# gesamtschaltung.net
KiCad netlist of a schematic drawn in EAGLE
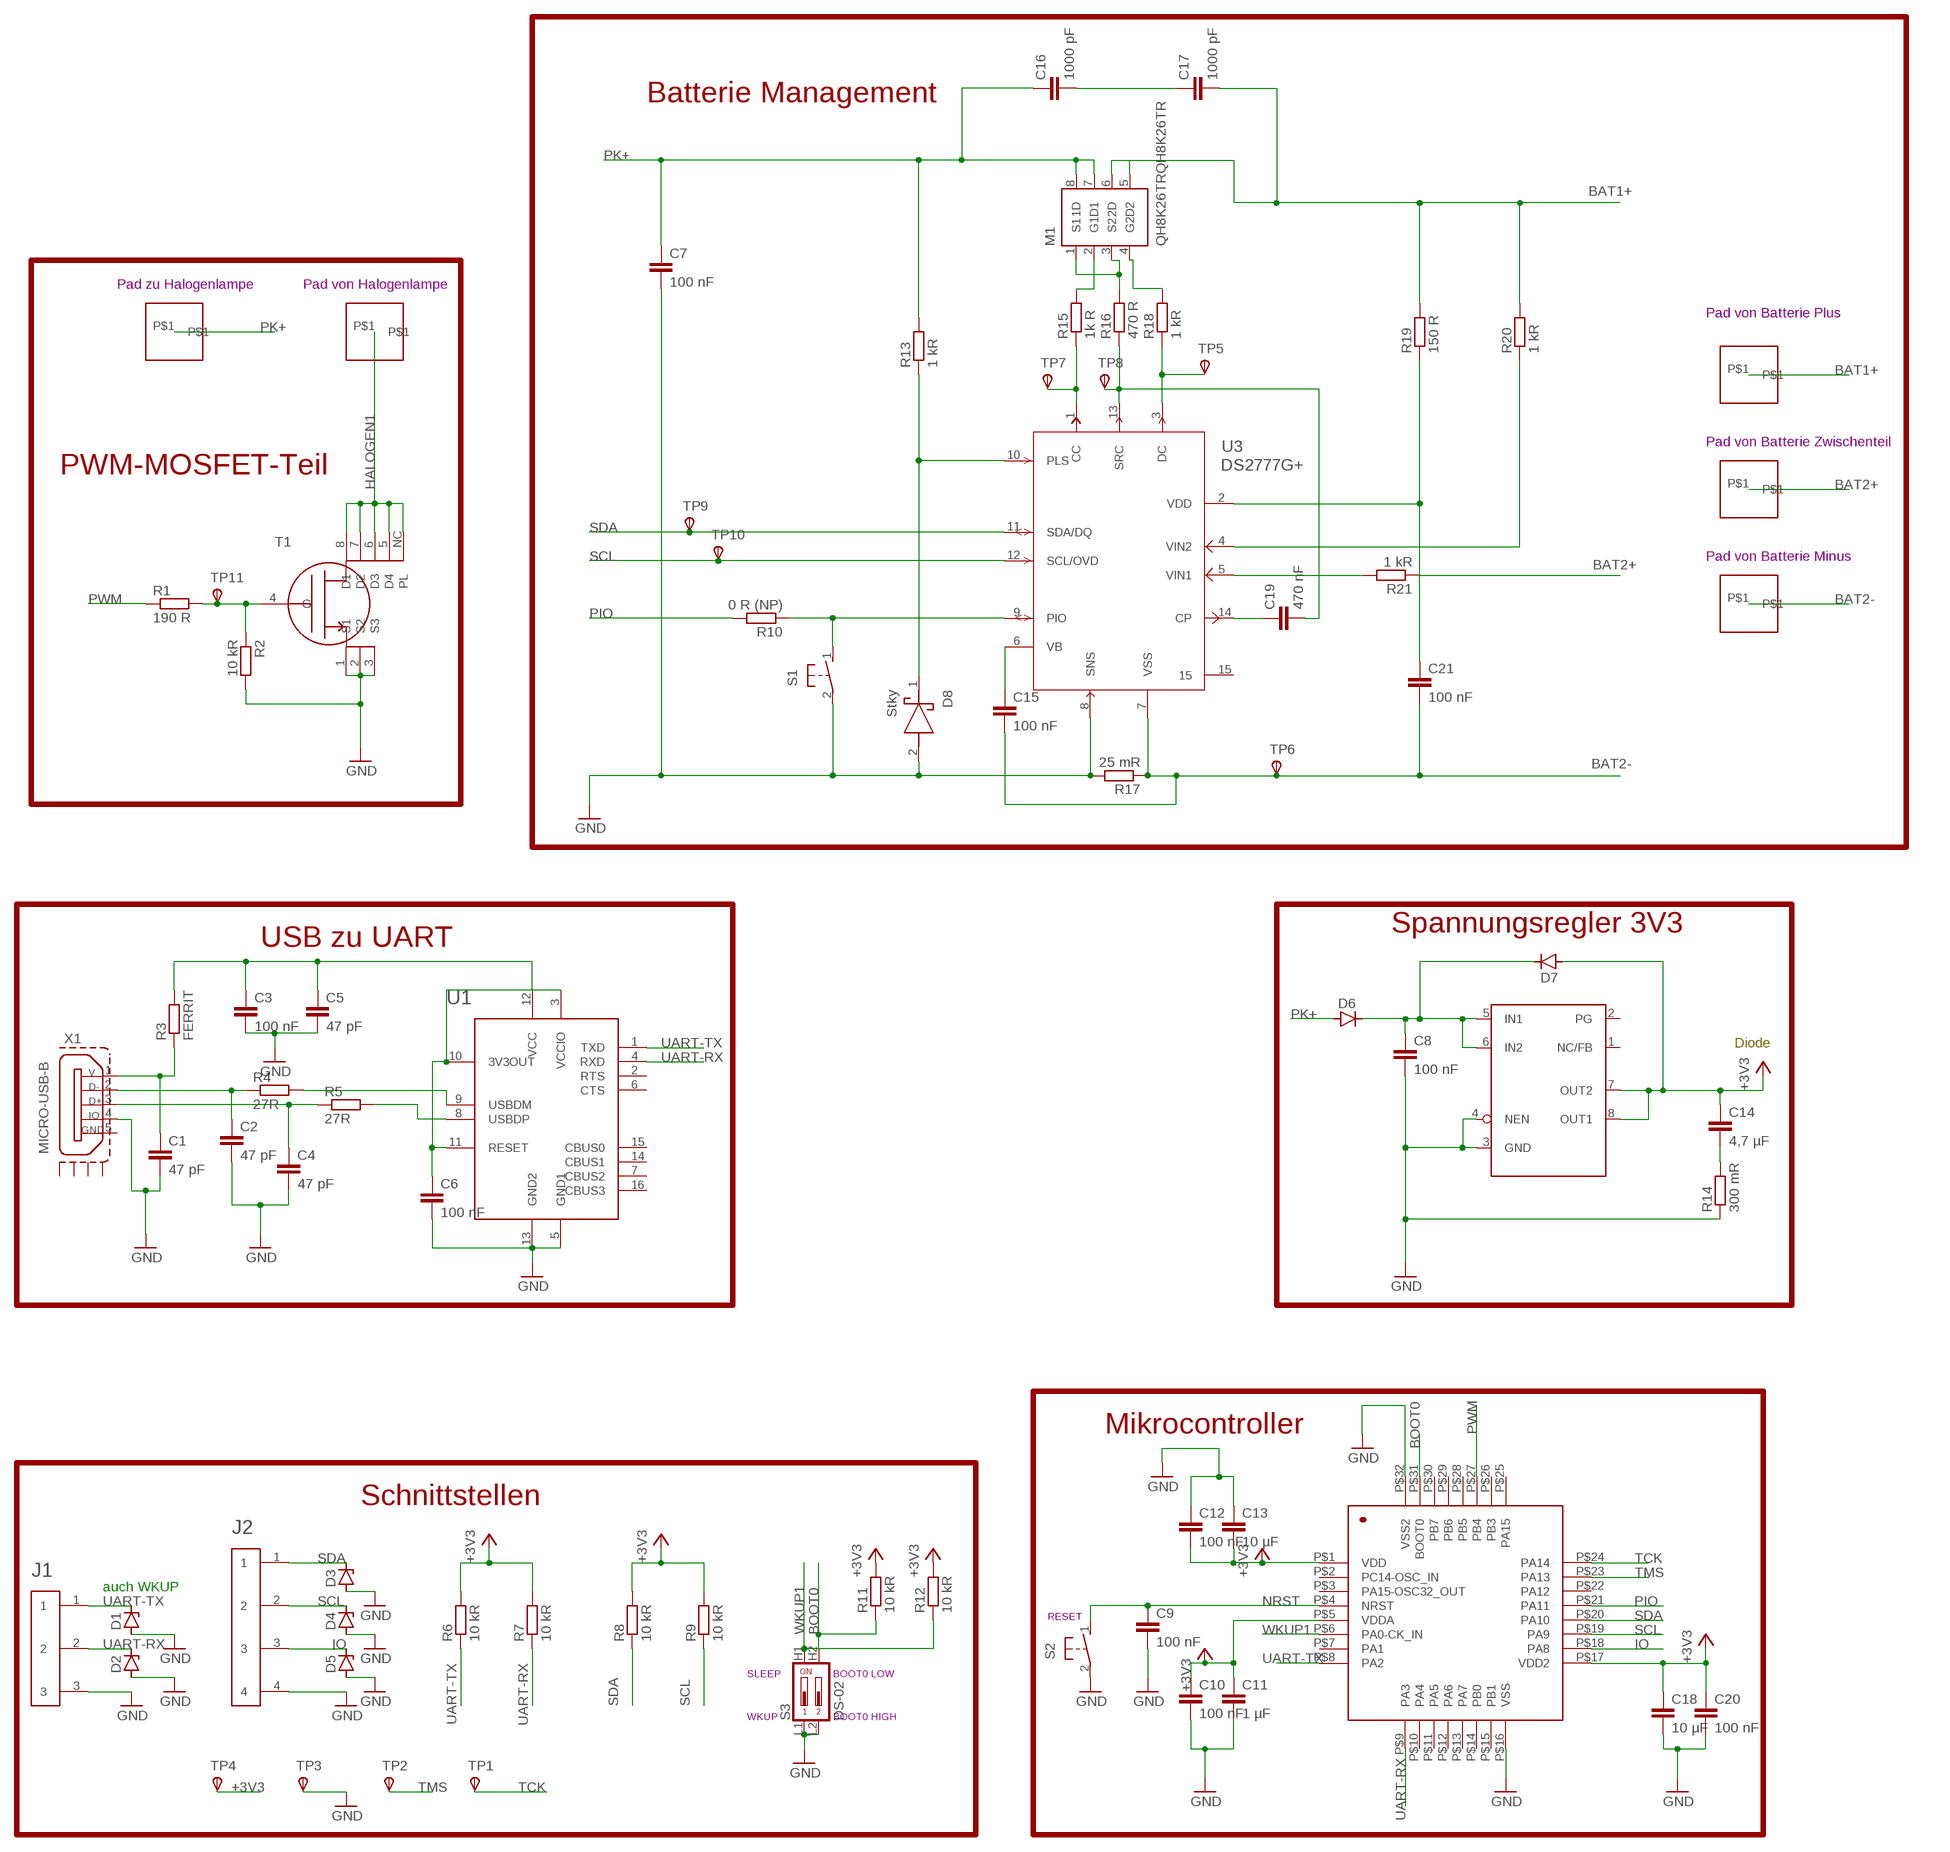
[diagram p0: schematic, sheet 1]

(export (version "E")
  (design (tool "Eeschema 10.0.6"))
  (components
    (comp (ref "C1")
      (value "47 pF")
      (footprint "eagle-import:C0603")
      (libsource (lib "eagle-import") (part "C-EUC0603"))
    )
    (comp (ref "C2")
      (value "47 pF")
      (footprint "eagle-import:C0603")
      (libsource (lib "eagle-import") (part "C-EUC0603"))
    )
    (comp (ref "C3")
      (value "100 nF")
      (footprint "eagle-import:C0603")
      (libsource (lib "eagle-import") (part "C-EUC0603"))
    )
    (comp (ref "C4")
      (value "47 pF")
      (footprint "eagle-import:C0603")
      (libsource (lib "eagle-import") (part "C-EUC0603"))
    )
    (comp (ref "C5")
      (value "47 pF")
      (footprint "eagle-import:C0603")
      (libsource (lib "eagle-import") (part "C-EUC0603"))
    )
    (comp (ref "C6")
      (value "100 nF")
      (footprint "eagle-import:C0603")
      (libsource (lib "eagle-import") (part "C-EUC0603"))
    )
    (comp (ref "C7")
      (value "100 nF")
      (footprint "eagle-import:C0603")
      (libsource (lib "eagle-import") (part "C-EUC0603"))
    )
    (comp (ref "C8")
      (value "100 nF")
      (footprint "eagle-import:C0603")
      (libsource (lib "eagle-import") (part "C-EUC0603"))
    )
    (comp (ref "C9")
      (value "100 nF")
      (footprint "eagle-import:C0603")
      (libsource (lib "eagle-import") (part "C-EUC0603"))
    )
    (comp (ref "C10")
      (value "100 nF")
      (footprint "eagle-import:C0603")
      (libsource (lib "eagle-import") (part "C-EUC0603"))
    )
    (comp (ref "C11")
      (value "1 µF")
      (footprint "eagle-import:C0603")
      (libsource (lib "eagle-import") (part "C-EUC0603"))
    )
    (comp (ref "C12")
      (value "100 nF")
      (footprint "eagle-import:C0603")
      (libsource (lib "eagle-import") (part "C-EUC0603"))
    )
    (comp (ref "C13")
      (value "10 µF")
      (footprint "eagle-import:C0603")
      (libsource (lib "eagle-import") (part "C-EUC0603"))
    )
    (comp (ref "C14")
      (value "4,7 µF")
      (footprint "eagle-import:C0603")
      (libsource (lib "eagle-import") (part "C-EUC0603"))
    )
    (comp (ref "C15")
      (value "100 nF")
      (footprint "eagle-import:C0603")
      (libsource (lib "eagle-import") (part "C-EUC0603"))
    )
    (comp (ref "C16")
      (value "1000 pF")
      (footprint "eagle-import:C0603")
      (libsource (lib "eagle-import") (part "C-EUC0603"))
    )
    (comp (ref "C17")
      (value "1000 pF")
      (footprint "eagle-import:C0603")
      (libsource (lib "eagle-import") (part "C-EUC0603"))
    )
    (comp (ref "C18")
      (value "10 µF")
      (footprint "eagle-import:C0603")
      (libsource (lib "eagle-import") (part "C-EUC0603"))
    )
    (comp (ref "C19")
      (value "470 nF")
      (footprint "eagle-import:C0603")
      (libsource (lib "eagle-import") (part "C-EUC0603"))
    )
    (comp (ref "C20")
      (value "100 nF")
      (footprint "eagle-import:C0603")
      (libsource (lib "eagle-import") (part "C-EUC0603"))
    )
    (comp (ref "C21")
      (value "100 nF")
      (footprint "eagle-import:C0603")
      (libsource (lib "eagle-import") (part "C-EUC0603"))
    )
    (comp (ref "D1")
      (value "TVS-3V5")
      (footprint "eagle-import:TVS-FOOT")
      (libsource (lib "eagle-import") (part "TVS-3V5"))
    )
    (comp (ref "D2")
      (value "TVS-3V5")
      (footprint "eagle-import:TVS-FOOT")
      (libsource (lib "eagle-import") (part "TVS-3V5"))
    )
    (comp (ref "D3")
      (value "TVS-3V5")
      (footprint "eagle-import:TVS-FOOT")
      (libsource (lib "eagle-import") (part "TVS-3V5"))
    )
    (comp (ref "D4")
      (value "TVS-3V5")
      (footprint "eagle-import:TVS-FOOT")
      (libsource (lib "eagle-import") (part "TVS-3V5"))
    )
    (comp (ref "D5")
      (value "TVS-3V5")
      (footprint "eagle-import:TVS-FOOT")
      (libsource (lib "eagle-import") (part "TVS-3V5"))
    )
    (comp (ref "D6")
      (value "DIODE-SILIZIUM")
      (footprint "eagle-import:TVS-FOOT")
      (libsource (lib "eagle-import") (part "DIODE-SILIZIUM"))
    )
    (comp (ref "D7")
      (value "DIODE-SILIZIUM")
      (footprint "eagle-import:TVS-FOOT")
      (libsource (lib "eagle-import") (part "DIODE-SILIZIUM"))
    )
    (comp (ref "D8")
      (value "Stky")
      (footprint "eagle-import:SOD3715X135N")
      (libsource (lib "eagle-import") (part "BAT54W-HG3-18SCHOTTKY"))
    )
    (comp (ref "J1")
      (value "3PIN")
      (footprint "eagle-import:HDRV3W64P254_1X3_762X254X854B")
      (libsource (lib "eagle-import") (part "3PIN"))
    )
    (comp (ref "J2")
      (value "4PIN-MALE")
      (footprint "eagle-import:4P-MALE-FOOT")
      (libsource (lib "eagle-import") (part "4PIN-MALE"))
    )
    (comp (ref "M1")
      (value "QH8K26TRQH8K26TR")
      (footprint "eagle-import:SOTFL65P280X85-8N")
      (libsource (lib "eagle-import") (part "QH8K26TRQH8K26TR"))
    )
    (comp (ref "MC1")
      (value "STM32L031K6T6")
      (footprint "eagle-import:LQFP32")
      (libsource (lib "eagle-import") (part "STM32L031K6T6"))
    )
    (comp (ref "P1")
      (value "PAD-3MM")
      (footprint "eagle-import:PAD-3MM")
      (libsource (lib "eagle-import") (part "PAD-3MM"))
    )
    (comp (ref "P2")
      (value "PAD-3MM")
      (footprint "eagle-import:PAD-3MM")
      (libsource (lib "eagle-import") (part "PAD-3MM"))
    )
    (comp (ref "P3")
      (value "PAD-3MM")
      (footprint "eagle-import:PAD-3MM")
      (libsource (lib "eagle-import") (part "PAD-3MM"))
    )
    (comp (ref "P4")
      (value "PAD-3MM")
      (footprint "eagle-import:PAD-3MM")
      (libsource (lib "eagle-import") (part "PAD-3MM"))
    )
    (comp (ref "P5")
      (value "PAD-3MM")
      (footprint "eagle-import:PAD-3MM")
      (libsource (lib "eagle-import") (part "PAD-3MM"))
    )
    (comp (ref "R1")
      (value "190 R")
      (footprint "eagle-import:R0603")
      (libsource (lib "eagle-import") (part "R-EU_R0603"))
    )
    (comp (ref "R2")
      (value "10 kR")
      (footprint "eagle-import:R0603")
      (libsource (lib "eagle-import") (part "R-EU_R0603"))
    )
    (comp (ref "R3")
      (value "FERRIT")
      (footprint "eagle-import:R0603")
      (libsource (lib "eagle-import") (part "R-EU_R0603"))
    )
    (comp (ref "R4")
      (value "27R")
      (footprint "eagle-import:R0603")
      (libsource (lib "eagle-import") (part "R-EU_R0603"))
    )
    (comp (ref "R5")
      (value "27R")
      (footprint "eagle-import:R0603")
      (libsource (lib "eagle-import") (part "R-EU_R0603"))
    )
    (comp (ref "R6")
      (value "10 kR")
      (footprint "eagle-import:R0603")
      (libsource (lib "eagle-import") (part "R-EU_R0603"))
    )
    (comp (ref "R7")
      (value "10 kR")
      (footprint "eagle-import:R0603")
      (libsource (lib "eagle-import") (part "R-EU_R0603"))
    )
    (comp (ref "R8")
      (value "10 kR")
      (footprint "eagle-import:R0603")
      (libsource (lib "eagle-import") (part "R-EU_R0603"))
    )
    (comp (ref "R9")
      (value "10 kR")
      (footprint "eagle-import:R0603")
      (libsource (lib "eagle-import") (part "R-EU_R0603"))
    )
    (comp (ref "R10")
      (value "0 R (NP)")
      (footprint "eagle-import:R0603")
      (libsource (lib "eagle-import") (part "R-EU_R0603"))
    )
    (comp (ref "R11")
      (value "10 kR")
      (footprint "eagle-import:R0603")
      (libsource (lib "eagle-import") (part "R-EU_R0603"))
    )
    (comp (ref "R12")
      (value "10 kR")
      (footprint "eagle-import:R0603")
      (libsource (lib "eagle-import") (part "R-EU_R0603"))
    )
    (comp (ref "R13")
      (value "1 kR")
      (footprint "eagle-import:R0603")
      (libsource (lib "eagle-import") (part "R-EU_R0603"))
    )
    (comp (ref "R14")
      (value "300 mR")
      (footprint "eagle-import:R0603")
      (libsource (lib "eagle-import") (part "R-EU_R0603"))
    )
    (comp (ref "R15")
      (value "1k R")
      (footprint "eagle-import:R0603")
      (libsource (lib "eagle-import") (part "R-EU_R0603"))
    )
    (comp (ref "R16")
      (value "470 R")
      (footprint "eagle-import:R0603")
      (libsource (lib "eagle-import") (part "R-EU_R0603"))
    )
    (comp (ref "R17")
      (value "25 mR")
      (footprint "eagle-import:R0603")
      (libsource (lib "eagle-import") (part "R-EU_R0603"))
    )
    (comp (ref "R18")
      (value "1 kR")
      (footprint "eagle-import:R0603")
      (libsource (lib "eagle-import") (part "R-EU_R0603"))
    )
    (comp (ref "R19")
      (value "150 R")
      (footprint "eagle-import:R0603")
      (libsource (lib "eagle-import") (part "R-EU_R0603"))
    )
    (comp (ref "R20")
      (value "1 kR")
      (footprint "eagle-import:R0603")
      (libsource (lib "eagle-import") (part "R-EU_R0603"))
    )
    (comp (ref "R21")
      (value "1 kR")
      (footprint "eagle-import:R0603")
      (libsource (lib "eagle-import") (part "R-EU_R0603"))
    )
    (comp (ref "S1")
      (value "BUTTON")
      (footprint "eagle-import:BUTTON")
      (libsource (lib "eagle-import") (part "BUTTON"))
    )
    (comp (ref "S2")
      (value "BUTTON")
      (footprint "eagle-import:BUTTON")
      (libsource (lib "eagle-import") (part "BUTTON"))
    )
    (comp (ref "S3")
      (value "DS-02")
      (footprint "eagle-import:DS-02")
      (libsource (lib "eagle-import") (part "DS-02"))
    )
    (comp (ref "T1")
      (value "POWER-MOS")
      (footprint "eagle-import:SO-8")
      (libsource (lib "eagle-import") (part "POWER-MOS"))
    )
    (comp (ref "TP1")
      (value "TPSTP20R")
      (footprint "eagle-import:TP20R")
      (libsource (lib "eagle-import") (part "TPSTP20R"))
    )
    (comp (ref "TP2")
      (value "TPSTP20R")
      (footprint "eagle-import:TP20R")
      (libsource (lib "eagle-import") (part "TPSTP20R"))
    )
    (comp (ref "TP3")
      (value "TPSTP20R")
      (footprint "eagle-import:TP20R")
      (libsource (lib "eagle-import") (part "TPSTP20R"))
    )
    (comp (ref "TP4")
      (value "TPSTP20R")
      (footprint "eagle-import:TP20R")
      (libsource (lib "eagle-import") (part "TPSTP20R"))
    )
    (comp (ref "TP5")
      (value "TPSTP10R")
      (footprint "eagle-import:TP10R")
      (libsource (lib "eagle-import") (part "TPSTP10R"))
    )
    (comp (ref "TP6")
      (value "TPSTP10R")
      (footprint "eagle-import:TP10R")
      (libsource (lib "eagle-import") (part "TPSTP10R"))
    )
    (comp (ref "TP7")
      (value "TPSTP10R")
      (footprint "eagle-import:TP10R")
      (libsource (lib "eagle-import") (part "TPSTP10R"))
    )
    (comp (ref "TP8")
      (value "TPSTP10R")
      (footprint "eagle-import:TP10R")
      (libsource (lib "eagle-import") (part "TPSTP10R"))
    )
    (comp (ref "TP9")
      (value "TPSTP10R")
      (footprint "eagle-import:TP10R")
      (libsource (lib "eagle-import") (part "TPSTP10R"))
    )
    (comp (ref "TP10")
      (value "TPSTP10R")
      (footprint "eagle-import:TP10R")
      (libsource (lib "eagle-import") (part "TPSTP10R"))
    )
    (comp (ref "TP11")
      (value "TPSTP10R")
      (footprint "eagle-import:TP10R")
      (libsource (lib "eagle-import") (part "TPSTP10R"))
    )
    (comp (ref "U1")
      (value "FT230X")
      (footprint "eagle-import:SSOP16")
      (libsource (lib "eagle-import") (part "FT230X"))
    )
    (comp (ref "U2")
      (value "TPS76633DR")
      (footprint "eagle-import:TPS766FOOTPRINT")
      (libsource (lib "eagle-import") (part "TPS76633DR"))
    )
    (comp (ref "U3")
      (value "DS2777G+")
      (footprint "eagle-import:DS2777_TDFN-15-OWN")
      (libsource (lib "eagle-import") (part "DS2777G+"))
    )
    (comp (ref "X1")
      (value "MICRO-USB-B")
      (footprint "eagle-import:MICROUSBFOOT")
      (libsource (lib "eagle-import") (part "MICRO-USB-B"))
    )
  )
  (nets
    (net (code "1") (name "+3V3") (class "Default")
      (node (ref "C10") (pin "1") (pinfunction "1_1") (pintype "passive"))
      (node (ref "C11") (pin "1") (pinfunction "1_1") (pintype "passive"))
      (node (ref "C12") (pin "2") (pinfunction "2_2") (pintype "passive"))
      (node (ref "C13") (pin "2") (pinfunction "2_2") (pintype "passive"))
      (node (ref "C14") (pin "1") (pinfunction "1_1") (pintype "passive"))
      (node (ref "C18") (pin "1") (pinfunction "1_1") (pintype "passive"))
      (node (ref "C20") (pin "1") (pinfunction "1_1") (pintype "passive"))
      (node (ref "D7") (pin "A") (pinfunction "A_A") (pintype "passive"))
      (node (ref "MC1") (pin "P$1") (pinfunction "VDD_P$1") (pintype "bidirectional"))
      (node (ref "MC1") (pin "P$17") (pinfunction "VDD2_P$17") (pintype "bidirectional"))
      (node (ref "MC1") (pin "P$5") (pinfunction "VDDA_P$5") (pintype "bidirectional"))
      (node (ref "R11") (pin "2") (pinfunction "2_2") (pintype "passive"))
      (node (ref "R12") (pin "2") (pinfunction "2_2") (pintype "passive"))
      (node (ref "R6") (pin "2") (pinfunction "2_2") (pintype "passive"))
      (node (ref "R7") (pin "2") (pinfunction "2_2") (pintype "passive"))
      (node (ref "R8") (pin "2") (pinfunction "2_2") (pintype "passive"))
      (node (ref "R9") (pin "2") (pinfunction "2_2") (pintype "passive"))
      (node (ref "TP4") (pin "TP") (pinfunction "PP_TP") (pintype "input"))
      (node (ref "U2") (pin "7") (pinfunction "OUT2_7") (pintype "bidirectional"))
      (node (ref "U2") (pin "8") (pinfunction "OUT1_8") (pintype "bidirectional"))
    )
    (net (code "2") (name "/BAT1+") (class "Default")
      (node (ref "C17") (pin "2") (pinfunction "2_2") (pintype "passive"))
      (node (ref "M1") (pin "5") (pinfunction "D2_5") (pintype "passive"))
      (node (ref "M1") (pin "6") (pinfunction "2D_6") (pintype "passive"))
      (node (ref "P3") (pin "P$1") (pinfunction "P$1_P$1") (pintype "bidirectional"))
      (node (ref "R19") (pin "2") (pinfunction "2_2") (pintype "passive"))
      (node (ref "R20") (pin "2") (pinfunction "2_2") (pintype "passive"))
    )
    (net (code "3") (name "/BAT2+") (class "Default")
      (node (ref "P4") (pin "P$1") (pinfunction "P$1_P$1") (pintype "bidirectional"))
      (node (ref "R21") (pin "1") (pinfunction "1_1") (pintype "passive"))
    )
    (net (code "4") (name "/BAT2-") (class "Default")
      (node (ref "C15") (pin "2") (pinfunction "2_2") (pintype "passive"))
      (node (ref "C21") (pin "2") (pinfunction "2_2") (pintype "passive"))
      (node (ref "P5") (pin "P$1") (pinfunction "P$1_P$1") (pintype "bidirectional"))
      (node (ref "R17") (pin "1") (pinfunction "1_1") (pintype "passive"))
      (node (ref "TP6") (pin "TP") (pinfunction "PP_TP") (pintype "input"))
      (node (ref "U3") (pin "7") (pinfunction "VSS_7") (pintype "power_in"))
    )
    (net (code "5") (name "/BOOT0") (class "Default")
      (node (ref "MC1") (pin "P$31") (pinfunction "BOOT0_P$31") (pintype "bidirectional"))
      (node (ref "R11") (pin "1") (pinfunction "1_1") (pintype "passive"))
      (node (ref "S3") (pin "H2") (pinfunction "H2_H2") (pintype "passive"))
    )
    (net (code "6") (name "/HALOGEN1") (class "Default")
      (node (ref "P2") (pin "P$1") (pinfunction "P$1_P$1") (pintype "bidirectional"))
      (node (ref "T1") (pin "5") (pinfunction "D4_5") (pintype "bidirectional"))
      (node (ref "T1") (pin "6") (pinfunction "D3_6") (pintype "bidirectional"))
      (node (ref "T1") (pin "7") (pinfunction "D2_7") (pintype "bidirectional"))
      (node (ref "T1") (pin "8") (pinfunction "D1_8") (pintype "bidirectional"))
      (node (ref "T1") (pin "NC") (pinfunction "PL_NC") (pintype "bidirectional"))
    )
    (net (code "7") (name "/IO") (class "Default")
      (node (ref "D5") (pin "K") (pinfunction "K_K") (pintype "passive"))
      (node (ref "J2") (pin "3") (pinfunction "3_3") (pintype "bidirectional"))
      (node (ref "MC1") (pin "P$18") (pinfunction "PA8_P$18") (pintype "bidirectional"))
    )
    (net (code "8") (name "/NRST") (class "Default")
      (node (ref "C9") (pin "1") (pinfunction "1_1") (pintype "passive"))
      (node (ref "MC1") (pin "P$4") (pinfunction "NRST_P$4") (pintype "bidirectional"))
      (node (ref "S2") (pin "1") (pinfunction "H_1") (pintype "passive"))
    )
    (net (code "9") (name "/PIO") (class "Default")
      (node (ref "MC1") (pin "P$21") (pinfunction "PA11_P$21") (pintype "bidirectional"))
      (node (ref "R10") (pin "2") (pinfunction "2_2") (pintype "passive"))
    )
    (net (code "10") (name "/PK+") (class "Default")
      (node (ref "C16") (pin "1") (pinfunction "1_1") (pintype "passive"))
      (node (ref "C7") (pin "1") (pinfunction "1_1") (pintype "passive"))
      (node (ref "D6") (pin "A") (pinfunction "A_A") (pintype "passive"))
      (node (ref "M1") (pin "7") (pinfunction "D1_7") (pintype "passive"))
      (node (ref "M1") (pin "8") (pinfunction "1D_8") (pintype "passive"))
      (node (ref "P1") (pin "P$1") (pinfunction "P$1_P$1") (pintype "bidirectional"))
      (node (ref "R13") (pin "2") (pinfunction "2_2") (pintype "passive"))
    )
    (net (code "11") (name "/PWM") (class "Default")
      (node (ref "MC1") (pin "P$27") (pinfunction "PB4_P$27") (pintype "bidirectional"))
      (node (ref "R1") (pin "1") (pinfunction "1_1") (pintype "passive"))
    )
    (net (code "12") (name "/SCL") (class "Default")
      (node (ref "D4") (pin "K") (pinfunction "K_K") (pintype "passive"))
      (node (ref "J2") (pin "2") (pinfunction "2_2") (pintype "bidirectional"))
      (node (ref "MC1") (pin "P$19") (pinfunction "PA9_P$19") (pintype "bidirectional"))
      (node (ref "R9") (pin "1") (pinfunction "1_1") (pintype "passive"))
      (node (ref "TP10") (pin "TP") (pinfunction "PP_TP") (pintype "input"))
      (node (ref "U3") (pin "12") (pinfunction "SCL/OVD_12") (pintype "input"))
    )
    (net (code "13") (name "/SDA") (class "Default")
      (node (ref "D3") (pin "K") (pinfunction "K_K") (pintype "passive"))
      (node (ref "J2") (pin "1") (pinfunction "1_1") (pintype "bidirectional"))
      (node (ref "MC1") (pin "P$20") (pinfunction "PA10_P$20") (pintype "bidirectional"))
      (node (ref "R8") (pin "1") (pinfunction "1_1") (pintype "passive"))
      (node (ref "TP9") (pin "TP") (pinfunction "PP_TP") (pintype "input"))
      (node (ref "U3") (pin "11") (pinfunction "SDA/DQ_11") (pintype "bidirectional"))
    )
    (net (code "14") (name "/TCK") (class "Default")
      (node (ref "MC1") (pin "P$24") (pinfunction "PA14_P$24") (pintype "bidirectional"))
      (node (ref "TP1") (pin "TP") (pinfunction "PP_TP") (pintype "input"))
    )
    (net (code "15") (name "/TMS") (class "Default")
      (node (ref "MC1") (pin "P$23") (pinfunction "PA13_P$23") (pintype "bidirectional"))
      (node (ref "TP2") (pin "TP") (pinfunction "PP_TP") (pintype "input"))
    )
    (net (code "16") (name "/UART-RX") (class "Default")
      (node (ref "D2") (pin "K") (pinfunction "K_K") (pintype "passive"))
      (node (ref "J1") (pin "2") (pinfunction "2_2") (pintype "bidirectional"))
      (node (ref "MC1") (pin "P$9") (pinfunction "PA3_P$9") (pintype "bidirectional"))
      (node (ref "R7") (pin "1") (pinfunction "1_1") (pintype "passive"))
      (node (ref "U1") (pin "4") (pinfunction "RXD_4") (pintype "bidirectional"))
    )
    (net (code "17") (name "/UART-TX") (class "Default")
      (node (ref "D1") (pin "K") (pinfunction "K_K") (pintype "passive"))
      (node (ref "J1") (pin "1") (pinfunction "1_1") (pintype "bidirectional"))
      (node (ref "MC1") (pin "P$8") (pinfunction "PA2_P$8") (pintype "bidirectional"))
      (node (ref "R6") (pin "1") (pinfunction "1_1") (pintype "passive"))
      (node (ref "U1") (pin "1") (pinfunction "TXD_1") (pintype "bidirectional"))
    )
    (net (code "18") (name "/WKUP1") (class "Default")
      (node (ref "MC1") (pin "P$6") (pinfunction "PA0-CK_IN_P$6") (pintype "bidirectional"))
      (node (ref "R12") (pin "1") (pinfunction "1_1") (pintype "passive"))
      (node (ref "S3") (pin "H1") (pinfunction "H1_H1") (pintype "passive"))
    )
    (net (code "19") (name "GND") (class "Default")
      (node (ref "C1") (pin "2") (pinfunction "2_2") (pintype "passive"))
      (node (ref "C10") (pin "2") (pinfunction "2_2") (pintype "passive"))
      (node (ref "C11") (pin "2") (pinfunction "2_2") (pintype "passive"))
      (node (ref "C12") (pin "1") (pinfunction "1_1") (pintype "passive"))
      (node (ref "C13") (pin "1") (pinfunction "1_1") (pintype "passive"))
      (node (ref "C18") (pin "2") (pinfunction "2_2") (pintype "passive"))
      (node (ref "C2") (pin "2") (pinfunction "2_2") (pintype "passive"))
      (node (ref "C20") (pin "2") (pinfunction "2_2") (pintype "passive"))
      (node (ref "C3") (pin "2") (pinfunction "2_2") (pintype "passive"))
      (node (ref "C4") (pin "2") (pinfunction "2_2") (pintype "passive"))
      (node (ref "C5") (pin "2") (pinfunction "2_2") (pintype "passive"))
      (node (ref "C6") (pin "2") (pinfunction "2_2") (pintype "passive"))
      (node (ref "C7") (pin "2") (pinfunction "2_2") (pintype "passive"))
      (node (ref "C8") (pin "2") (pinfunction "2_2") (pintype "passive"))
      (node (ref "C9") (pin "2") (pinfunction "2_2") (pintype "passive"))
      (node (ref "D1") (pin "A") (pinfunction "A_A") (pintype "passive"))
      (node (ref "D2") (pin "A") (pinfunction "A_A") (pintype "passive"))
      (node (ref "D3") (pin "A") (pinfunction "A_A") (pintype "passive"))
      (node (ref "D4") (pin "A") (pinfunction "A_A") (pintype "passive"))
      (node (ref "D5") (pin "A") (pinfunction "A_A") (pintype "passive"))
      (node (ref "D8") (pin "2") (pinfunction "A_2") (pintype "bidirectional"))
      (node (ref "J1") (pin "3") (pinfunction "3_3") (pintype "bidirectional"))
      (node (ref "J2") (pin "4") (pinfunction "4_4") (pintype "bidirectional"))
      (node (ref "MC1") (pin "P$16") (pinfunction "VSS_P$16") (pintype "bidirectional"))
      (node (ref "MC1") (pin "P$32") (pinfunction "VSS2_P$32") (pintype "bidirectional"))
      (node (ref "R14") (pin "1") (pinfunction "1_1") (pintype "passive"))
      (node (ref "R17") (pin "2") (pinfunction "2_2") (pintype "passive"))
      (node (ref "R2") (pin "2") (pinfunction "2_2") (pintype "passive"))
      (node (ref "S1") (pin "2") (pinfunction "L_2") (pintype "passive"))
      (node (ref "S2") (pin "2") (pinfunction "L_2") (pintype "passive"))
      (node (ref "S3") (pin "L1") (pinfunction "L1_L1") (pintype "passive"))
      (node (ref "S3") (pin "L2") (pinfunction "L2_L2") (pintype "passive"))
      (node (ref "T1") (pin "1") (pinfunction "S1_1") (pintype "bidirectional"))
      (node (ref "T1") (pin "2") (pinfunction "S2_2") (pintype "bidirectional"))
      (node (ref "T1") (pin "3") (pinfunction "S3_3") (pintype "bidirectional"))
      (node (ref "TP3") (pin "TP") (pinfunction "PP_TP") (pintype "input"))
      (node (ref "U1") (pin "13") (pinfunction "GND2_13") (pintype "bidirectional"))
      (node (ref "U1") (pin "5") (pinfunction "GND1_5") (pintype "bidirectional"))
      (node (ref "U2") (pin "3") (pinfunction "GND_3") (pintype "bidirectional"))
      (node (ref "U2") (pin "4") (pinfunction "NEN_4") (pintype "bidirectional"))
      (node (ref "U3") (pin "8") (pinfunction "SNS_8") (pintype "input"))
      (node (ref "X1") (pin "4") (pinfunction "IO_4") (pintype "passive"))
    )
    (net (code "20") (name "Net-(C14-Pad2)") (class "Default")
      (node (ref "C14") (pin "2") (pinfunction "2_2") (pintype "passive"))
      (node (ref "R14") (pin "2") (pinfunction "2_2") (pintype "passive"))
    )
    (net (code "21") (name "Net-(C16-Pad2)") (class "Default")
      (node (ref "C16") (pin "2") (pinfunction "2_2") (pintype "passive"))
      (node (ref "C17") (pin "1") (pinfunction "1_1") (pintype "passive"))
    )
    (net (code "22") (name "Net-(D8-K)") (class "Default")
      (node (ref "D8") (pin "1") (pinfunction "K_1") (pintype "bidirectional"))
      (node (ref "R13") (pin "1") (pinfunction "1_1") (pintype "passive"))
      (node (ref "U3") (pin "10") (pinfunction "PLS_10") (pintype "input"))
    )
    (net (code "23") (name "Net-(M1-G1)") (class "Default")
      (node (ref "M1") (pin "2") (pinfunction "G1_2") (pintype "passive"))
      (node (ref "R15") (pin "2") (pinfunction "2_2") (pintype "passive"))
    )
    (net (code "24") (name "Net-(M1-G2)") (class "Default")
      (node (ref "M1") (pin "4") (pinfunction "G2_4") (pintype "passive"))
      (node (ref "R18") (pin "2") (pinfunction "2_2") (pintype "passive"))
    )
    (net (code "25") (name "Net-(M1-S1)") (class "Default")
      (node (ref "M1") (pin "1") (pinfunction "S1_1") (pintype "passive"))
      (node (ref "M1") (pin "3") (pinfunction "S2_3") (pintype "passive"))
      (node (ref "R16") (pin "2") (pinfunction "2_2") (pintype "passive"))
    )
    (net (code "26") (name "Net-(S1-H)") (class "Default")
      (node (ref "R10") (pin "1") (pinfunction "1_1") (pintype "passive"))
      (node (ref "S1") (pin "1") (pinfunction "H_1") (pintype "passive"))
      (node (ref "U3") (pin "9") (pinfunction "PIO_9") (pintype "bidirectional"))
    )
    (net (code "27") (name "Net-(T1-G)") (class "Default")
      (node (ref "R1") (pin "2") (pinfunction "2_2") (pintype "passive"))
      (node (ref "R2") (pin "1") (pinfunction "1_1") (pintype "passive"))
      (node (ref "T1") (pin "4") (pinfunction "G_4") (pintype "bidirectional"))
      (node (ref "TP11") (pin "TP") (pinfunction "PP_TP") (pintype "input"))
    )
    (net (code "28") (name "Net-(TP5-PP)") (class "Default")
      (node (ref "R18") (pin "1") (pinfunction "1_1") (pintype "passive"))
      (node (ref "TP5") (pin "TP") (pinfunction "PP_TP") (pintype "input"))
      (node (ref "U3") (pin "3") (pinfunction "DC_3") (pintype "output"))
    )
    (net (code "29") (name "Net-(TP7-PP)") (class "Default")
      (node (ref "R15") (pin "1") (pinfunction "1_1") (pintype "passive"))
      (node (ref "TP7") (pin "TP") (pinfunction "PP_TP") (pintype "input"))
      (node (ref "U3") (pin "1") (pinfunction "CC_1") (pintype "output"))
    )
    (net (code "30") (name "Net-(TP8-PP)") (class "Default")
      (node (ref "C19") (pin "2") (pinfunction "2_2") (pintype "passive"))
      (node (ref "R16") (pin "1") (pinfunction "1_1") (pintype "passive"))
      (node (ref "TP8") (pin "TP") (pinfunction "PP_TP") (pintype "input"))
      (node (ref "U3") (pin "13") (pinfunction "SRC_13") (pintype "passive"))
    )
    (net (code "31") (name "Net-(U1-3V3OUT)") (class "Default")
      (node (ref "C6") (pin "1") (pinfunction "1_1") (pintype "passive"))
      (node (ref "U1") (pin "10") (pinfunction "3V3OUT_10") (pintype "bidirectional"))
      (node (ref "U1") (pin "11") (pinfunction "RESET_11") (pintype "bidirectional"))
      (node (ref "U1") (pin "3") (pinfunction "VCCIO_3") (pintype "bidirectional"))
    )
    (net (code "32") (name "Net-(U1-USBDM)") (class "Default")
      (node (ref "R4") (pin "2") (pinfunction "2_2") (pintype "passive"))
      (node (ref "U1") (pin "9") (pinfunction "USBDM_9") (pintype "bidirectional"))
    )
    (net (code "33") (name "Net-(U1-USBDP)") (class "Default")
      (node (ref "R5") (pin "2") (pinfunction "2_2") (pintype "passive"))
      (node (ref "U1") (pin "8") (pinfunction "USBDP_8") (pintype "bidirectional"))
    )
    (net (code "34") (name "Net-(U1-VCC)") (class "Default")
      (node (ref "C3") (pin "1") (pinfunction "1_1") (pintype "passive"))
      (node (ref "C5") (pin "1") (pinfunction "1_1") (pintype "passive"))
      (node (ref "R3") (pin "2") (pinfunction "2_2") (pintype "passive"))
      (node (ref "U1") (pin "12") (pinfunction "VCC_12") (pintype "bidirectional"))
    )
    (net (code "35") (name "Net-(U2-IN1)") (class "Default")
      (node (ref "C8") (pin "1") (pinfunction "1_1") (pintype "passive"))
      (node (ref "D6") (pin "K") (pinfunction "K_K") (pintype "passive"))
      (node (ref "D7") (pin "K") (pinfunction "K_K") (pintype "passive"))
      (node (ref "U2") (pin "5") (pinfunction "IN1_5") (pintype "bidirectional"))
      (node (ref "U2") (pin "6") (pinfunction "IN2_6") (pintype "bidirectional"))
    )
    (net (code "36") (name "Net-(U3-CP)") (class "Default")
      (node (ref "C19") (pin "1") (pinfunction "1_1") (pintype "passive"))
      (node (ref "U3") (pin "14") (pinfunction "CP_14") (pintype "output"))
    )
    (net (code "37") (name "Net-(U3-VB)") (class "Default")
      (node (ref "C15") (pin "1") (pinfunction "1_1") (pintype "passive"))
      (node (ref "U3") (pin "6") (pinfunction "VB_6") (pintype "power_in"))
    )
    (net (code "38") (name "Net-(U3-VDD)") (class "Default")
      (node (ref "C21") (pin "1") (pinfunction "1_1") (pintype "passive"))
      (node (ref "R19") (pin "1") (pinfunction "1_1") (pintype "passive"))
      (node (ref "U3") (pin "2") (pinfunction "VDD_2") (pintype "power_in"))
    )
    (net (code "39") (name "Net-(U3-VIN1)") (class "Default")
      (node (ref "R21") (pin "2") (pinfunction "2_2") (pintype "passive"))
      (node (ref "U3") (pin "5") (pinfunction "VIN1_5") (pintype "input"))
    )
    (net (code "40") (name "Net-(U3-VIN2)") (class "Default")
      (node (ref "R20") (pin "1") (pinfunction "1_1") (pintype "passive"))
      (node (ref "U3") (pin "4") (pinfunction "VIN2_4") (pintype "input"))
    )
    (net (code "41") (name "Net-(X1-D+)") (class "Default")
      (node (ref "C4") (pin "1") (pinfunction "1_1") (pintype "passive"))
      (node (ref "R5") (pin "1") (pinfunction "1_1") (pintype "passive"))
      (node (ref "X1") (pin "3") (pinfunction "D+_3") (pintype "passive"))
    )
    (net (code "42") (name "Net-(X1-D-)") (class "Default")
      (node (ref "C2") (pin "1") (pinfunction "1_1") (pintype "passive"))
      (node (ref "R4") (pin "1") (pinfunction "1_1") (pintype "passive"))
      (node (ref "X1") (pin "2") (pinfunction "D-_2") (pintype "passive"))
    )
    (net (code "43") (name "Net-(X1-V)") (class "Default")
      (node (ref "C1") (pin "1") (pinfunction "1_1") (pintype "passive"))
      (node (ref "R3") (pin "1") (pinfunction "1_1") (pintype "passive"))
      (node (ref "X1") (pin "1") (pinfunction "V_1") (pintype "passive"))
    )
    (net (code "44") (name "unconnected-(MC1-PA1-PadP$7)") (class "Default")
      (node (ref "MC1") (pin "P$7") (pinfunction "PA1_P$7") (pintype "bidirectional"))
    )
    (net (code "45") (name "unconnected-(MC1-PA4-PadP$10)") (class "Default")
      (node (ref "MC1") (pin "P$10") (pinfunction "PA4_P$10") (pintype "bidirectional"))
    )
    (net (code "46") (name "unconnected-(MC1-PA5-PadP$11)") (class "Default")
      (node (ref "MC1") (pin "P$11") (pinfunction "PA5_P$11") (pintype "bidirectional"))
    )
    (net (code "47") (name "unconnected-(MC1-PA6-PadP$12)") (class "Default")
      (node (ref "MC1") (pin "P$12") (pinfunction "PA6_P$12") (pintype "bidirectional"))
    )
    (net (code "48") (name "unconnected-(MC1-PA7-PadP$13)") (class "Default")
      (node (ref "MC1") (pin "P$13") (pinfunction "PA7_P$13") (pintype "bidirectional"))
    )
    (net (code "49") (name "unconnected-(MC1-PA12-PadP$22)") (class "Default")
      (node (ref "MC1") (pin "P$22") (pinfunction "PA12_P$22") (pintype "bidirectional"))
    )
    (net (code "50") (name "unconnected-(MC1-PA15-OSC32_OUT-PadP$3)") (class "Default")
      (node (ref "MC1") (pin "P$3") (pinfunction "PA15-OSC32_OUT_P$3") (pintype "bidirectional"))
    )
    (net (code "51") (name "unconnected-(MC1-PA15-PadP$25)") (class "Default")
      (node (ref "MC1") (pin "P$25") (pinfunction "PA15_P$25") (pintype "bidirectional"))
    )
    (net (code "52") (name "unconnected-(MC1-PB0-PadP$14)") (class "Default")
      (node (ref "MC1") (pin "P$14") (pinfunction "PB0_P$14") (pintype "bidirectional"))
    )
    (net (code "53") (name "unconnected-(MC1-PB1-PadP$15)") (class "Default")
      (node (ref "MC1") (pin "P$15") (pinfunction "PB1_P$15") (pintype "bidirectional"))
    )
    (net (code "54") (name "unconnected-(MC1-PB3-PadP$26)") (class "Default")
      (node (ref "MC1") (pin "P$26") (pinfunction "PB3_P$26") (pintype "bidirectional"))
    )
    (net (code "55") (name "unconnected-(MC1-PB5-PadP$28)") (class "Default")
      (node (ref "MC1") (pin "P$28") (pinfunction "PB5_P$28") (pintype "bidirectional"))
    )
    (net (code "56") (name "unconnected-(MC1-PB6-PadP$29)") (class "Default")
      (node (ref "MC1") (pin "P$29") (pinfunction "PB6_P$29") (pintype "bidirectional"))
    )
    (net (code "57") (name "unconnected-(MC1-PB7-PadP$30)") (class "Default")
      (node (ref "MC1") (pin "P$30") (pinfunction "PB7_P$30") (pintype "bidirectional"))
    )
    (net (code "58") (name "unconnected-(MC1-PC14-OSC_IN-PadP$2)") (class "Default")
      (node (ref "MC1") (pin "P$2") (pinfunction "PC14-OSC_IN_P$2") (pintype "bidirectional"))
    )
    (net (code "59") (name "unconnected-(U1-CBUS0-Pad15)") (class "Default")
      (node (ref "U1") (pin "15") (pinfunction "CBUS0_15") (pintype "bidirectional"))
    )
    (net (code "60") (name "unconnected-(U1-CBUS1-Pad14)") (class "Default")
      (node (ref "U1") (pin "14") (pinfunction "CBUS1_14") (pintype "bidirectional"))
    )
    (net (code "61") (name "unconnected-(U1-CBUS2-Pad7)") (class "Default")
      (node (ref "U1") (pin "7") (pinfunction "CBUS2_7") (pintype "bidirectional"))
    )
    (net (code "62") (name "unconnected-(U1-CBUS3-Pad16)") (class "Default")
      (node (ref "U1") (pin "16") (pinfunction "CBUS3_16") (pintype "bidirectional"))
    )
    (net (code "63") (name "unconnected-(U1-CTS-Pad6)") (class "Default")
      (node (ref "U1") (pin "6") (pinfunction "CTS_6") (pintype "bidirectional"))
    )
    (net (code "64") (name "unconnected-(U1-RTS-Pad2)") (class "Default")
      (node (ref "U1") (pin "2") (pinfunction "RTS_2") (pintype "bidirectional"))
    )
    (net (code "65") (name "unconnected-(U2-NC{slash}FB-Pad1)") (class "Default")
      (node (ref "U2") (pin "1") (pinfunction "NC/FB_1") (pintype "bidirectional"))
    )
    (net (code "66") (name "unconnected-(U2-PG-Pad2)") (class "Default")
      (node (ref "U2") (pin "2") (pinfunction "PG_2") (pintype "bidirectional"))
    )
    (net (code "67") (name "unconnected-(U3-Pad15)") (class "Default")
      (node (ref "U3") (pin "15") (pinfunction "15_15") (pintype "passive"))
    )
    (net (code "68") (name "unconnected-(X1-GND-Pad5)") (class "Default")
      (node (ref "X1") (pin "5") (pinfunction "GND_5") (pintype "passive"))
    )
    (net (code "69") (name "unconnected-(X1-PadS1)") (class "Default")
      (node (ref "X1") (pin "S1") (pinfunction "S1_S1") (pintype "passive"))
    )
    (net (code "70") (name "unconnected-(X1-PadS2)") (class "Default")
      (node (ref "X1") (pin "S2") (pinfunction "S2_S2") (pintype "passive"))
    )
    (net (code "71") (name "unconnected-(X1-PadS3)") (class "Default")
      (node (ref "X1") (pin "S3") (pinfunction "S3_S3") (pintype "passive"))
    )
    (net (code "72") (name "unconnected-(X1-PadS4)") (class "Default")
      (node (ref "X1") (pin "S4") (pinfunction "S4_S4") (pintype "passive"))
    )
  )
)
